# pla251715.net
KiCad netlist of a schematic drawn in EAGLE
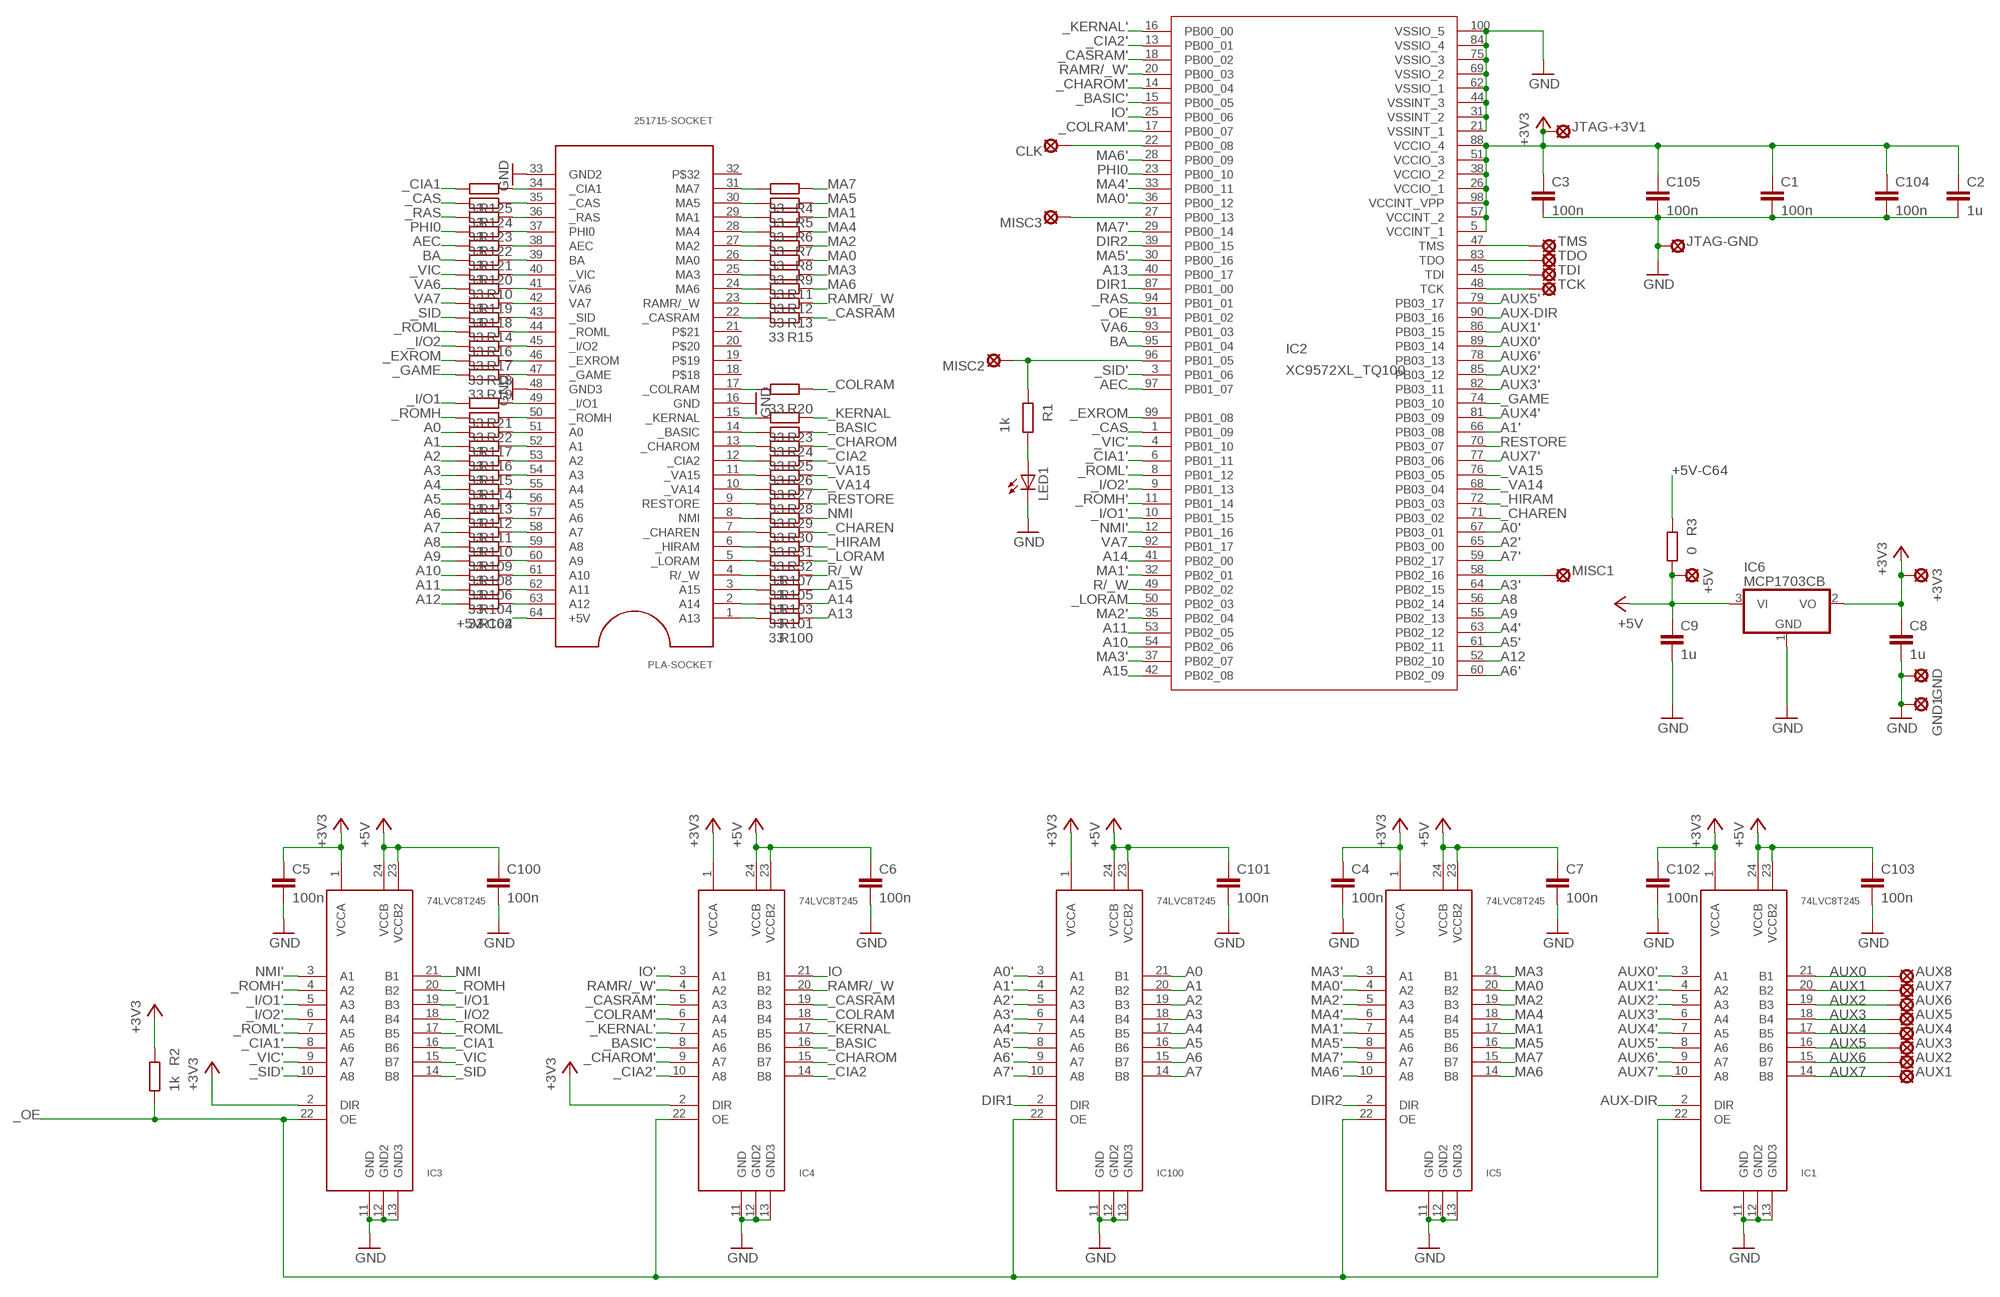
[diagram p0: schematic, sheet 1]

(export (version "E")
  (design (tool "Eeschema 10.0.6"))
  (components
    (comp (ref "+3V3")
      (value "LSP10")
      (footprint "eagle-import:LSP10")
      (libsource (lib "eagle-import") (part "LSP10"))
    )
    (comp (ref "+5V")
      (value "LSP10")
      (footprint "eagle-import:LSP10")
      (libsource (lib "eagle-import") (part "LSP10"))
    )
    (comp (ref "AUX1")
      (value "LSP10")
      (footprint "eagle-import:LSP10")
      (libsource (lib "eagle-import") (part "LSP10"))
    )
    (comp (ref "AUX2")
      (value "LSP10")
      (footprint "eagle-import:LSP10")
      (libsource (lib "eagle-import") (part "LSP10"))
    )
    (comp (ref "AUX3")
      (value "LSP10")
      (footprint "eagle-import:LSP10")
      (libsource (lib "eagle-import") (part "LSP10"))
    )
    (comp (ref "AUX4")
      (value "LSP10")
      (footprint "eagle-import:LSP10")
      (libsource (lib "eagle-import") (part "LSP10"))
    )
    (comp (ref "AUX5")
      (value "LSP10")
      (footprint "eagle-import:LSP10")
      (libsource (lib "eagle-import") (part "LSP10"))
    )
    (comp (ref "AUX6")
      (value "LSP10")
      (footprint "eagle-import:LSP10")
      (libsource (lib "eagle-import") (part "LSP10"))
    )
    (comp (ref "AUX7")
      (value "LSP10")
      (footprint "eagle-import:LSP10")
      (libsource (lib "eagle-import") (part "LSP10"))
    )
    (comp (ref "AUX8")
      (value "LSP10")
      (footprint "eagle-import:LSP10")
      (libsource (lib "eagle-import") (part "LSP10"))
    )
    (comp (ref "C1")
      (value "100n")
      (footprint "eagle-import:C0603")
      (libsource (lib "eagle-import") (part "C-EUC0603"))
    )
    (comp (ref "C2")
      (value "1u")
      (footprint "eagle-import:C1210")
      (libsource (lib "eagle-import") (part "C-EUC1210"))
    )
    (comp (ref "C3")
      (value "100n")
      (footprint "eagle-import:C0603")
      (libsource (lib "eagle-import") (part "C-EUC0603"))
    )
    (comp (ref "C4")
      (value "100n")
      (footprint "eagle-import:C0603")
      (libsource (lib "eagle-import") (part "C-EUC0603"))
    )
    (comp (ref "C5")
      (value "100n")
      (footprint "eagle-import:C0603")
      (libsource (lib "eagle-import") (part "C-EUC0603"))
    )
    (comp (ref "C6")
      (value "100n")
      (footprint "eagle-import:C0603")
      (libsource (lib "eagle-import") (part "C-EUC0603"))
    )
    (comp (ref "C7")
      (value "100n")
      (footprint "eagle-import:C0603")
      (libsource (lib "eagle-import") (part "C-EUC0603"))
    )
    (comp (ref "C8")
      (value "1u")
      (footprint "eagle-import:C1210")
      (libsource (lib "eagle-import") (part "C-EUC1210"))
    )
    (comp (ref "C9")
      (value "1u")
      (footprint "eagle-import:C1210")
      (libsource (lib "eagle-import") (part "C-EUC1210"))
    )
    (comp (ref "C100")
      (value "100n")
      (footprint "eagle-import:C0603")
      (libsource (lib "eagle-import") (part "C-EUC0603"))
    )
    (comp (ref "C101")
      (value "100n")
      (footprint "eagle-import:C0603")
      (libsource (lib "eagle-import") (part "C-EUC0603"))
    )
    (comp (ref "C102")
      (value "100n")
      (footprint "eagle-import:C0603")
      (libsource (lib "eagle-import") (part "C-EUC0603"))
    )
    (comp (ref "C103")
      (value "100n")
      (footprint "eagle-import:C0603")
      (libsource (lib "eagle-import") (part "C-EUC0603"))
    )
    (comp (ref "C104")
      (value "100n")
      (footprint "eagle-import:C0603")
      (libsource (lib "eagle-import") (part "C-EUC0603"))
    )
    (comp (ref "C105")
      (value "100n")
      (footprint "eagle-import:C0603")
      (libsource (lib "eagle-import") (part "C-EUC0603"))
    )
    (comp (ref "CLK")
      (value "LSP10")
      (footprint "eagle-import:LSP10")
      (libsource (lib "eagle-import") (part "LSP10"))
    )
    (comp (ref "GND")
      (value "LSP10")
      (footprint "eagle-import:LSP10")
      (libsource (lib "eagle-import") (part "LSP10"))
    )
    (comp (ref "GND1")
      (value "LSP10")
      (footprint "eagle-import:LSP10")
      (libsource (lib "eagle-import") (part "LSP10"))
    )
    (comp (ref "IC1")
      (value "74LVC8T245")
      (footprint "eagle-import:TSSOP24")
      (libsource (lib "eagle-import") (part "74LVC8T245"))
    )
    (comp (ref "IC2")
      (value "XC9572XL_TQ100")
      (footprint "eagle-import:TQ100")
      (libsource (lib "eagle-import") (part "XC9572XL_TQ100"))
    )
    (comp (ref "IC3")
      (value "74LVC8T245")
      (footprint "eagle-import:TSSOP24")
      (libsource (lib "eagle-import") (part "74LVC8T245"))
    )
    (comp (ref "IC4")
      (value "74LVC8T245")
      (footprint "eagle-import:TSSOP24")
      (libsource (lib "eagle-import") (part "74LVC8T245"))
    )
    (comp (ref "IC5")
      (value "74LVC8T245")
      (footprint "eagle-import:TSSOP24")
      (libsource (lib "eagle-import") (part "74LVC8T245"))
    )
    (comp (ref "IC6")
      (value "MCP1703CB")
      (footprint "eagle-import:SOT23")
      (libsource (lib "eagle-import") (part "MCP1703CB"))
    )
    (comp (ref "IC100")
      (value "74LVC8T245")
      (footprint "eagle-import:TSSOP24")
      (libsource (lib "eagle-import") (part "74LVC8T245"))
    )
    (comp (ref "JTAG-+3V1")
      (value "LSP10")
      (footprint "eagle-import:LSP10")
      (libsource (lib "eagle-import") (part "LSP10"))
    )
    (comp (ref "JTAG-GND")
      (value "LSP10")
      (footprint "eagle-import:LSP10")
      (libsource (lib "eagle-import") (part "LSP10"))
    )
    (comp (ref "LED1")
      (value "LED5MM")
      (footprint "eagle-import:LED5MM")
      (libsource (lib "eagle-import") (part "LED5MM"))
    )
    (comp (ref "MISC1")
      (value "LSP10")
      (footprint "eagle-import:LSP10")
      (libsource (lib "eagle-import") (part "LSP10"))
    )
    (comp (ref "MISC2")
      (value "LSP10")
      (footprint "eagle-import:LSP10")
      (libsource (lib "eagle-import") (part "LSP10"))
    )
    (comp (ref "MISC3")
      (value "LSP10")
      (footprint "eagle-import:LSP10")
      (libsource (lib "eagle-import") (part "LSP10"))
    )
    (comp (ref "PLA-SOCKET")
      (value "251715-SOCKET")
      (footprint "eagle-import:64-SPDIP")
      (libsource (lib "eagle-import") (part "251715-SOCKET"))
    )
    (comp (ref "R1")
      (value "1k")
      (footprint "eagle-import:R0805")
      (libsource (lib "eagle-import") (part "R-EU_R0805"))
    )
    (comp (ref "R2")
      (value "1k")
      (footprint "eagle-import:R0805")
      (libsource (lib "eagle-import") (part "R-EU_R0805"))
    )
    (comp (ref "R3")
      (value "0")
      (footprint "eagle-import:R0805")
      (libsource (lib "eagle-import") (part "R-EU_R0805"))
    )
    (comp (ref "R4")
      (value "33")
      (footprint "eagle-import:R0402")
      (libsource (lib "eagle-import") (part "R-EU_R0402"))
    )
    (comp (ref "R5")
      (value "33")
      (footprint "eagle-import:R0402")
      (libsource (lib "eagle-import") (part "R-EU_R0402"))
    )
    (comp (ref "R6")
      (value "33")
      (footprint "eagle-import:R0402")
      (libsource (lib "eagle-import") (part "R-EU_R0402"))
    )
    (comp (ref "R7")
      (value "33")
      (footprint "eagle-import:R0402")
      (libsource (lib "eagle-import") (part "R-EU_R0402"))
    )
    (comp (ref "R8")
      (value "33")
      (footprint "eagle-import:R0402")
      (libsource (lib "eagle-import") (part "R-EU_R0402"))
    )
    (comp (ref "R9")
      (value "33")
      (footprint "eagle-import:R0402")
      (libsource (lib "eagle-import") (part "R-EU_R0402"))
    )
    (comp (ref "R10")
      (value "33")
      (footprint "eagle-import:R0402")
      (libsource (lib "eagle-import") (part "R-EU_R0402"))
    )
    (comp (ref "R11")
      (value "33")
      (footprint "eagle-import:R0402")
      (libsource (lib "eagle-import") (part "R-EU_R0402"))
    )
    (comp (ref "R12")
      (value "33")
      (footprint "eagle-import:R0402")
      (libsource (lib "eagle-import") (part "R-EU_R0402"))
    )
    (comp (ref "R13")
      (value "33")
      (footprint "eagle-import:R0402")
      (libsource (lib "eagle-import") (part "R-EU_R0402"))
    )
    (comp (ref "R14")
      (value "33")
      (footprint "eagle-import:R0402")
      (libsource (lib "eagle-import") (part "R-EU_R0402"))
    )
    (comp (ref "R15")
      (value "33")
      (footprint "eagle-import:R0402")
      (libsource (lib "eagle-import") (part "R-EU_R0402"))
    )
    (comp (ref "R16")
      (value "33")
      (footprint "eagle-import:R0402")
      (libsource (lib "eagle-import") (part "R-EU_R0402"))
    )
    (comp (ref "R17")
      (value "33")
      (footprint "eagle-import:R0402")
      (libsource (lib "eagle-import") (part "R-EU_R0402"))
    )
    (comp (ref "R18")
      (value "33")
      (footprint "eagle-import:R0402")
      (libsource (lib "eagle-import") (part "R-EU_R0402"))
    )
    (comp (ref "R19")
      (value "33")
      (footprint "eagle-import:R0402")
      (libsource (lib "eagle-import") (part "R-EU_R0402"))
    )
    (comp (ref "R20")
      (value "33")
      (footprint "eagle-import:R0402")
      (libsource (lib "eagle-import") (part "R-EU_R0402"))
    )
    (comp (ref "R21")
      (value "33")
      (footprint "eagle-import:R0402")
      (libsource (lib "eagle-import") (part "R-EU_R0402"))
    )
    (comp (ref "R22")
      (value "33")
      (footprint "eagle-import:R0402")
      (libsource (lib "eagle-import") (part "R-EU_R0402"))
    )
    (comp (ref "R23")
      (value "33")
      (footprint "eagle-import:R0402")
      (libsource (lib "eagle-import") (part "R-EU_R0402"))
    )
    (comp (ref "R24")
      (value "33")
      (footprint "eagle-import:R0402")
      (libsource (lib "eagle-import") (part "R-EU_R0402"))
    )
    (comp (ref "R25")
      (value "33")
      (footprint "eagle-import:R0402")
      (libsource (lib "eagle-import") (part "R-EU_R0402"))
    )
    (comp (ref "R26")
      (value "33")
      (footprint "eagle-import:R0402")
      (libsource (lib "eagle-import") (part "R-EU_R0402"))
    )
    (comp (ref "R27")
      (value "33")
      (footprint "eagle-import:R0402")
      (libsource (lib "eagle-import") (part "R-EU_R0402"))
    )
    (comp (ref "R28")
      (value "33")
      (footprint "eagle-import:R0402")
      (libsource (lib "eagle-import") (part "R-EU_R0402"))
    )
    (comp (ref "R29")
      (value "33")
      (footprint "eagle-import:R0402")
      (libsource (lib "eagle-import") (part "R-EU_R0402"))
    )
    (comp (ref "R30")
      (value "33")
      (footprint "eagle-import:R0402")
      (libsource (lib "eagle-import") (part "R-EU_R0402"))
    )
    (comp (ref "R31")
      (value "33")
      (footprint "eagle-import:R0402")
      (libsource (lib "eagle-import") (part "R-EU_R0402"))
    )
    (comp (ref "R32")
      (value "33")
      (footprint "eagle-import:R0402")
      (libsource (lib "eagle-import") (part "R-EU_R0402"))
    )
    (comp (ref "R100")
      (value "33")
      (footprint "eagle-import:R0402")
      (libsource (lib "eagle-import") (part "R-EU_R0402"))
    )
    (comp (ref "R101")
      (value "33")
      (footprint "eagle-import:R0402")
      (libsource (lib "eagle-import") (part "R-EU_R0402"))
    )
    (comp (ref "R102")
      (value "33")
      (footprint "eagle-import:R0402")
      (libsource (lib "eagle-import") (part "R-EU_R0402"))
    )
    (comp (ref "R103")
      (value "33")
      (footprint "eagle-import:R0402")
      (libsource (lib "eagle-import") (part "R-EU_R0402"))
    )
    (comp (ref "R104")
      (value "33")
      (footprint "eagle-import:R0402")
      (libsource (lib "eagle-import") (part "R-EU_R0402"))
    )
    (comp (ref "R105")
      (value "33")
      (footprint "eagle-import:R0402")
      (libsource (lib "eagle-import") (part "R-EU_R0402"))
    )
    (comp (ref "R106")
      (value "33")
      (footprint "eagle-import:R0402")
      (libsource (lib "eagle-import") (part "R-EU_R0402"))
    )
    (comp (ref "R107")
      (value "33")
      (footprint "eagle-import:R0402")
      (libsource (lib "eagle-import") (part "R-EU_R0402"))
    )
    (comp (ref "R108")
      (value "33")
      (footprint "eagle-import:R0402")
      (libsource (lib "eagle-import") (part "R-EU_R0402"))
    )
    (comp (ref "R109")
      (value "33")
      (footprint "eagle-import:R0402")
      (libsource (lib "eagle-import") (part "R-EU_R0402"))
    )
    (comp (ref "R110")
      (value "33")
      (footprint "eagle-import:R0402")
      (libsource (lib "eagle-import") (part "R-EU_R0402"))
    )
    (comp (ref "R111")
      (value "33")
      (footprint "eagle-import:R0402")
      (libsource (lib "eagle-import") (part "R-EU_R0402"))
    )
    (comp (ref "R112")
      (value "33")
      (footprint "eagle-import:R0402")
      (libsource (lib "eagle-import") (part "R-EU_R0402"))
    )
    (comp (ref "R113")
      (value "33")
      (footprint "eagle-import:R0402")
      (libsource (lib "eagle-import") (part "R-EU_R0402"))
    )
    (comp (ref "R114")
      (value "33")
      (footprint "eagle-import:R0402")
      (libsource (lib "eagle-import") (part "R-EU_R0402"))
    )
    (comp (ref "R115")
      (value "33")
      (footprint "eagle-import:R0402")
      (libsource (lib "eagle-import") (part "R-EU_R0402"))
    )
    (comp (ref "R116")
      (value "33")
      (footprint "eagle-import:R0402")
      (libsource (lib "eagle-import") (part "R-EU_R0402"))
    )
    (comp (ref "R117")
      (value "33")
      (footprint "eagle-import:R0402")
      (libsource (lib "eagle-import") (part "R-EU_R0402"))
    )
    (comp (ref "R118")
      (value "33")
      (footprint "eagle-import:R0402")
      (libsource (lib "eagle-import") (part "R-EU_R0402"))
    )
    (comp (ref "R119")
      (value "33")
      (footprint "eagle-import:R0402")
      (libsource (lib "eagle-import") (part "R-EU_R0402"))
    )
    (comp (ref "R120")
      (value "33")
      (footprint "eagle-import:R0402")
      (libsource (lib "eagle-import") (part "R-EU_R0402"))
    )
    (comp (ref "R121")
      (value "33")
      (footprint "eagle-import:R0402")
      (libsource (lib "eagle-import") (part "R-EU_R0402"))
    )
    (comp (ref "R122")
      (value "33")
      (footprint "eagle-import:R0402")
      (libsource (lib "eagle-import") (part "R-EU_R0402"))
    )
    (comp (ref "R123")
      (value "33")
      (footprint "eagle-import:R0402")
      (libsource (lib "eagle-import") (part "R-EU_R0402"))
    )
    (comp (ref "R124")
      (value "33")
      (footprint "eagle-import:R0402")
      (libsource (lib "eagle-import") (part "R-EU_R0402"))
    )
    (comp (ref "R125")
      (value "33")
      (footprint "eagle-import:R0402")
      (libsource (lib "eagle-import") (part "R-EU_R0402"))
    )
    (comp (ref "TCK")
      (value "LSP10")
      (footprint "eagle-import:LSP10")
      (libsource (lib "eagle-import") (part "LSP10"))
    )
    (comp (ref "TDI")
      (value "LSP10")
      (footprint "eagle-import:LSP10")
      (libsource (lib "eagle-import") (part "LSP10"))
    )
    (comp (ref "TDO")
      (value "LSP10")
      (footprint "eagle-import:LSP10")
      (libsource (lib "eagle-import") (part "LSP10"))
    )
    (comp (ref "TMS")
      (value "LSP10")
      (footprint "eagle-import:LSP10")
      (libsource (lib "eagle-import") (part "LSP10"))
    )
  )
  (nets
    (net (code "1") (name "+3V3") (class "Default")
      (node (ref "+3V3") (pin "MP") (pinfunction "MP_MP") (pintype "passive"))
      (node (ref "C1") (pin "1") (pinfunction "1_1") (pintype "passive"))
      (node (ref "C102") (pin "1") (pinfunction "1_1") (pintype "passive"))
      (node (ref "C104") (pin "1") (pinfunction "1_1") (pintype "passive"))
      (node (ref "C105") (pin "1") (pinfunction "1_1") (pintype "passive"))
      (node (ref "C2") (pin "1") (pinfunction "1_1") (pintype "passive"))
      (node (ref "C3") (pin "1") (pinfunction "1_1") (pintype "passive"))
      (node (ref "C4") (pin "1") (pinfunction "1_1") (pintype "passive"))
      (node (ref "C5") (pin "1") (pinfunction "1_1") (pintype "passive"))
      (node (ref "C8") (pin "1") (pinfunction "1_1") (pintype "passive"))
      (node (ref "IC1") (pin "1") (pinfunction "VCCA_1") (pintype "bidirectional"))
      (node (ref "IC100") (pin "1") (pinfunction "VCCA_1") (pintype "bidirectional"))
      (node (ref "IC2") (pin "26") (pinfunction "VCCIO_1_26") (pintype "passive"))
      (node (ref "IC2") (pin "38") (pinfunction "VCCIO_2_38") (pintype "passive"))
      (node (ref "IC2") (pin "5") (pinfunction "VCCINT_1_5") (pintype "passive"))
      (node (ref "IC2") (pin "51") (pinfunction "VCCIO_3_51") (pintype "passive"))
      (node (ref "IC2") (pin "57") (pinfunction "VCCINT_2_57") (pintype "passive"))
      (node (ref "IC2") (pin "88") (pinfunction "VCCIO_4_88") (pintype "passive"))
      (node (ref "IC2") (pin "98") (pinfunction "VCCINT_VPP_98") (pintype "passive"))
      (node (ref "IC3") (pin "1") (pinfunction "VCCA_1") (pintype "bidirectional"))
      (node (ref "IC3") (pin "2") (pinfunction "DIR_2") (pintype "bidirectional"))
      (node (ref "IC4") (pin "1") (pinfunction "VCCA_1") (pintype "bidirectional"))
      (node (ref "IC4") (pin "2") (pinfunction "DIR_2") (pintype "bidirectional"))
      (node (ref "IC5") (pin "1") (pinfunction "VCCA_1") (pintype "bidirectional"))
      (node (ref "IC6") (pin "2") (pinfunction "VO_2") (pintype "passive"))
      (node (ref "JTAG-+3V1") (pin "MP") (pinfunction "MP_MP") (pintype "passive"))
      (node (ref "R2") (pin "1") (pinfunction "1_1") (pintype "passive"))
    )
    (net (code "2") (name "+5V") (class "Default")
      (node (ref "+5V") (pin "MP") (pinfunction "MP_MP") (pintype "passive"))
      (node (ref "C100") (pin "1") (pinfunction "1_1") (pintype "passive"))
      (node (ref "C101") (pin "1") (pinfunction "1_1") (pintype "passive"))
      (node (ref "C103") (pin "1") (pinfunction "1_1") (pintype "passive"))
      (node (ref "C6") (pin "1") (pinfunction "1_1") (pintype "passive"))
      (node (ref "C7") (pin "1") (pinfunction "1_1") (pintype "passive"))
      (node (ref "C9") (pin "1") (pinfunction "1_1") (pintype "passive"))
      (node (ref "IC1") (pin "23") (pinfunction "VCCB2_23") (pintype "bidirectional"))
      (node (ref "IC1") (pin "24") (pinfunction "VCCB_24") (pintype "bidirectional"))
      (node (ref "IC100") (pin "23") (pinfunction "VCCB2_23") (pintype "bidirectional"))
      (node (ref "IC100") (pin "24") (pinfunction "VCCB_24") (pintype "bidirectional"))
      (node (ref "IC3") (pin "23") (pinfunction "VCCB2_23") (pintype "bidirectional"))
      (node (ref "IC3") (pin "24") (pinfunction "VCCB_24") (pintype "bidirectional"))
      (node (ref "IC4") (pin "23") (pinfunction "VCCB2_23") (pintype "bidirectional"))
      (node (ref "IC4") (pin "24") (pinfunction "VCCB_24") (pintype "bidirectional"))
      (node (ref "IC5") (pin "23") (pinfunction "VCCB2_23") (pintype "bidirectional"))
      (node (ref "IC5") (pin "24") (pinfunction "VCCB_24") (pintype "bidirectional"))
      (node (ref "IC6") (pin "3") (pinfunction "VI_3") (pintype "input"))
      (node (ref "R3") (pin "2") (pinfunction "2_2") (pintype "passive"))
    )
    (net (code "3") (name "/+5V-C64") (class "Default")
      (node (ref "PLA-SOCKET") (pin "64") (pinfunction "+5V_64") (pintype "bidirectional"))
      (node (ref "R3") (pin "1") (pinfunction "1_1") (pintype "passive"))
    )
    (net (code "4") (name "/A0") (class "Default")
      (node (ref "IC100") (pin "21") (pinfunction "B1_21") (pintype "bidirectional"))
      (node (ref "R117") (pin "2") (pinfunction "2_2") (pintype "passive"))
    )
    (net (code "5") (name "/A0'") (class "Default")
      (node (ref "IC100") (pin "3") (pinfunction "A1_3") (pintype "bidirectional"))
      (node (ref "IC2") (pin "67") (pinfunction "PB03_01_67") (pintype "bidirectional"))
    )
    (net (code "6") (name "/A1") (class "Default")
      (node (ref "IC100") (pin "20") (pinfunction "B2_20") (pintype "bidirectional"))
      (node (ref "R116") (pin "2") (pinfunction "2_2") (pintype "passive"))
    )
    (net (code "7") (name "/A1'") (class "Default")
      (node (ref "IC100") (pin "4") (pinfunction "A2_4") (pintype "bidirectional"))
      (node (ref "IC2") (pin "66") (pinfunction "PB03_08_66") (pintype "bidirectional"))
    )
    (net (code "8") (name "/A2") (class "Default")
      (node (ref "IC100") (pin "19") (pinfunction "B3_19") (pintype "bidirectional"))
      (node (ref "R115") (pin "2") (pinfunction "2_2") (pintype "passive"))
    )
    (net (code "9") (name "/A2'") (class "Default")
      (node (ref "IC100") (pin "5") (pinfunction "A3_5") (pintype "bidirectional"))
      (node (ref "IC2") (pin "65") (pinfunction "PB03_00_65") (pintype "bidirectional"))
    )
    (net (code "10") (name "/A3") (class "Default")
      (node (ref "IC100") (pin "18") (pinfunction "B4_18") (pintype "bidirectional"))
      (node (ref "R114") (pin "2") (pinfunction "2_2") (pintype "passive"))
    )
    (net (code "11") (name "/A3'") (class "Default")
      (node (ref "IC100") (pin "6") (pinfunction "A4_6") (pintype "bidirectional"))
      (node (ref "IC2") (pin "64") (pinfunction "PB02_15_64") (pintype "bidirectional"))
    )
    (net (code "12") (name "/A4") (class "Default")
      (node (ref "IC100") (pin "17") (pinfunction "B5_17") (pintype "bidirectional"))
      (node (ref "R113") (pin "2") (pinfunction "2_2") (pintype "passive"))
    )
    (net (code "13") (name "/A4'") (class "Default")
      (node (ref "IC100") (pin "7") (pinfunction "A5_7") (pintype "bidirectional"))
      (node (ref "IC2") (pin "63") (pinfunction "PB02_12_63") (pintype "bidirectional"))
    )
    (net (code "14") (name "/A5") (class "Default")
      (node (ref "IC100") (pin "16") (pinfunction "B6_16") (pintype "bidirectional"))
      (node (ref "R112") (pin "2") (pinfunction "2_2") (pintype "passive"))
    )
    (net (code "15") (name "/A5'") (class "Default")
      (node (ref "IC100") (pin "8") (pinfunction "A6_8") (pintype "bidirectional"))
      (node (ref "IC2") (pin "61") (pinfunction "PB02_11_61") (pintype "bidirectional"))
    )
    (net (code "16") (name "/A6") (class "Default")
      (node (ref "IC100") (pin "15") (pinfunction "B7_15") (pintype "bidirectional"))
      (node (ref "R111") (pin "2") (pinfunction "2_2") (pintype "passive"))
    )
    (net (code "17") (name "/A6'") (class "Default")
      (node (ref "IC100") (pin "9") (pinfunction "A7_9") (pintype "bidirectional"))
      (node (ref "IC2") (pin "60") (pinfunction "PB02_09_60") (pintype "bidirectional"))
    )
    (net (code "18") (name "/A7") (class "Default")
      (node (ref "IC100") (pin "14") (pinfunction "B8_14") (pintype "bidirectional"))
      (node (ref "R110") (pin "2") (pinfunction "2_2") (pintype "passive"))
    )
    (net (code "19") (name "/A7'") (class "Default")
      (node (ref "IC100") (pin "10") (pinfunction "A8_10") (pintype "bidirectional"))
      (node (ref "IC2") (pin "59") (pinfunction "PB02_17_59") (pintype "bidirectional"))
    )
    (net (code "20") (name "/A8") (class "Default")
      (node (ref "IC2") (pin "56") (pinfunction "PB02_14_56") (pintype "bidirectional"))
      (node (ref "R109") (pin "2") (pinfunction "2_2") (pintype "passive"))
    )
    (net (code "21") (name "/A9") (class "Default")
      (node (ref "IC2") (pin "55") (pinfunction "PB02_13_55") (pintype "bidirectional"))
      (node (ref "R108") (pin "2") (pinfunction "2_2") (pintype "passive"))
    )
    (net (code "22") (name "/A10") (class "Default")
      (node (ref "IC2") (pin "54") (pinfunction "PB02_06_54") (pintype "bidirectional"))
      (node (ref "R106") (pin "2") (pinfunction "2_2") (pintype "passive"))
    )
    (net (code "23") (name "/A11") (class "Default")
      (node (ref "IC2") (pin "53") (pinfunction "PB02_05_53") (pintype "bidirectional"))
      (node (ref "R104") (pin "2") (pinfunction "2_2") (pintype "passive"))
    )
    (net (code "24") (name "/A12") (class "Default")
      (node (ref "IC2") (pin "52") (pinfunction "PB02_10_52") (pintype "bidirectional"))
      (node (ref "R102") (pin "2") (pinfunction "2_2") (pintype "passive"))
    )
    (net (code "25") (name "/A13") (class "Default")
      (node (ref "IC2") (pin "40") (pinfunction "PB00_17_40") (pintype "bidirectional"))
      (node (ref "R100") (pin "1") (pinfunction "1_1") (pintype "passive"))
    )
    (net (code "26") (name "/A14") (class "Default")
      (node (ref "IC2") (pin "41") (pinfunction "PB02_00_41") (pintype "bidirectional"))
      (node (ref "R101") (pin "1") (pinfunction "1_1") (pintype "passive"))
    )
    (net (code "27") (name "/A15") (class "Default")
      (node (ref "IC2") (pin "42") (pinfunction "PB02_08_42") (pintype "bidirectional"))
      (node (ref "R103") (pin "1") (pinfunction "1_1") (pintype "passive"))
    )
    (net (code "28") (name "/AEC") (class "Default")
      (node (ref "IC2") (pin "97") (pinfunction "PB01_07_97") (pintype "bidirectional"))
      (node (ref "R121") (pin "2") (pinfunction "2_2") (pintype "passive"))
    )
    (net (code "29") (name "/AUX-DIR") (class "Default")
      (node (ref "IC1") (pin "2") (pinfunction "DIR_2") (pintype "bidirectional"))
      (node (ref "IC2") (pin "90") (pinfunction "PB03_16_90") (pintype "bidirectional"))
    )
    (net (code "30") (name "/AUX0") (class "Default")
      (node (ref "AUX8") (pin "MP") (pinfunction "MP_MP") (pintype "passive"))
      (node (ref "IC1") (pin "21") (pinfunction "B1_21") (pintype "bidirectional"))
    )
    (net (code "31") (name "/AUX0'") (class "Default")
      (node (ref "IC1") (pin "3") (pinfunction "A1_3") (pintype "bidirectional"))
      (node (ref "IC2") (pin "89") (pinfunction "PB03_14_89") (pintype "bidirectional"))
    )
    (net (code "32") (name "/AUX1") (class "Default")
      (node (ref "AUX7") (pin "MP") (pinfunction "MP_MP") (pintype "passive"))
      (node (ref "IC1") (pin "20") (pinfunction "B2_20") (pintype "bidirectional"))
    )
    (net (code "33") (name "/AUX1'") (class "Default")
      (node (ref "IC1") (pin "4") (pinfunction "A2_4") (pintype "bidirectional"))
      (node (ref "IC2") (pin "86") (pinfunction "PB03_15_86") (pintype "bidirectional"))
    )
    (net (code "34") (name "/AUX2") (class "Default")
      (node (ref "AUX6") (pin "MP") (pinfunction "MP_MP") (pintype "passive"))
      (node (ref "IC1") (pin "19") (pinfunction "B3_19") (pintype "bidirectional"))
    )
    (net (code "35") (name "/AUX2'") (class "Default")
      (node (ref "IC1") (pin "5") (pinfunction "A3_5") (pintype "bidirectional"))
      (node (ref "IC2") (pin "85") (pinfunction "PB03_12_85") (pintype "bidirectional"))
    )
    (net (code "36") (name "/AUX3") (class "Default")
      (node (ref "AUX5") (pin "MP") (pinfunction "MP_MP") (pintype "passive"))
      (node (ref "IC1") (pin "18") (pinfunction "B4_18") (pintype "bidirectional"))
    )
    (net (code "37") (name "/AUX3'") (class "Default")
      (node (ref "IC1") (pin "6") (pinfunction "A4_6") (pintype "bidirectional"))
      (node (ref "IC2") (pin "82") (pinfunction "PB03_11_82") (pintype "bidirectional"))
    )
    (net (code "38") (name "/AUX4") (class "Default")
      (node (ref "AUX4") (pin "MP") (pinfunction "MP_MP") (pintype "passive"))
      (node (ref "IC1") (pin "17") (pinfunction "B5_17") (pintype "bidirectional"))
    )
    (net (code "39") (name "/AUX4'") (class "Default")
      (node (ref "IC1") (pin "7") (pinfunction "A5_7") (pintype "bidirectional"))
      (node (ref "IC2") (pin "81") (pinfunction "PB03_09_81") (pintype "bidirectional"))
    )
    (net (code "40") (name "/AUX5") (class "Default")
      (node (ref "AUX3") (pin "MP") (pinfunction "MP_MP") (pintype "passive"))
      (node (ref "IC1") (pin "16") (pinfunction "B6_16") (pintype "bidirectional"))
    )
    (net (code "41") (name "/AUX5'") (class "Default")
      (node (ref "IC1") (pin "8") (pinfunction "A6_8") (pintype "bidirectional"))
      (node (ref "IC2") (pin "79") (pinfunction "PB03_17_79") (pintype "bidirectional"))
    )
    (net (code "42") (name "/AUX6") (class "Default")
      (node (ref "AUX2") (pin "MP") (pinfunction "MP_MP") (pintype "passive"))
      (node (ref "IC1") (pin "15") (pinfunction "B7_15") (pintype "bidirectional"))
    )
    (net (code "43") (name "/AUX6'") (class "Default")
      (node (ref "IC1") (pin "9") (pinfunction "A7_9") (pintype "bidirectional"))
      (node (ref "IC2") (pin "78") (pinfunction "PB03_13_78") (pintype "bidirectional"))
    )
    (net (code "44") (name "/AUX7") (class "Default")
      (node (ref "AUX1") (pin "MP") (pinfunction "MP_MP") (pintype "passive"))
      (node (ref "IC1") (pin "14") (pinfunction "B8_14") (pintype "bidirectional"))
    )
    (net (code "45") (name "/AUX7'") (class "Default")
      (node (ref "IC1") (pin "10") (pinfunction "A8_10") (pintype "bidirectional"))
      (node (ref "IC2") (pin "77") (pinfunction "PB03_06_77") (pintype "bidirectional"))
    )
    (net (code "46") (name "/BA") (class "Default")
      (node (ref "IC2") (pin "95") (pinfunction "PB01_04_95") (pintype "bidirectional"))
      (node (ref "R120") (pin "2") (pinfunction "2_2") (pintype "passive"))
    )
    (net (code "47") (name "/DIR1") (class "Default")
      (node (ref "IC100") (pin "2") (pinfunction "DIR_2") (pintype "bidirectional"))
      (node (ref "IC2") (pin "87") (pinfunction "PB01_00_87") (pintype "bidirectional"))
    )
    (net (code "48") (name "/DIR2") (class "Default")
      (node (ref "IC2") (pin "39") (pinfunction "PB00_15_39") (pintype "bidirectional"))
      (node (ref "IC5") (pin "2") (pinfunction "DIR_2") (pintype "bidirectional"))
    )
    (net (code "49") (name "/IO") (class "Default")
      (node (ref "IC4") (pin "21") (pinfunction "B1_21") (pintype "bidirectional"))
    )
    (net (code "50") (name "/IO'") (class "Default")
      (node (ref "IC2") (pin "25") (pinfunction "PB00_06_25") (pintype "bidirectional"))
      (node (ref "IC4") (pin "3") (pinfunction "A1_3") (pintype "bidirectional"))
    )
    (net (code "51") (name "/MA0") (class "Default")
      (node (ref "IC5") (pin "20") (pinfunction "B2_20") (pintype "bidirectional"))
      (node (ref "R9") (pin "1") (pinfunction "1_1") (pintype "passive"))
    )
    (net (code "52") (name "/MA0'") (class "Default")
      (node (ref "IC2") (pin "36") (pinfunction "PB00_12_36") (pintype "bidirectional"))
      (node (ref "IC5") (pin "4") (pinfunction "A2_4") (pintype "bidirectional"))
    )
    (net (code "53") (name "/MA1") (class "Default")
      (node (ref "IC5") (pin "17") (pinfunction "B5_17") (pintype "bidirectional"))
      (node (ref "R6") (pin "1") (pinfunction "1_1") (pintype "passive"))
    )
    (net (code "54") (name "/MA1'") (class "Default")
      (node (ref "IC2") (pin "32") (pinfunction "PB02_01_32") (pintype "bidirectional"))
      (node (ref "IC5") (pin "7") (pinfunction "A5_7") (pintype "bidirectional"))
    )
    (net (code "55") (name "/MA2") (class "Default")
      (node (ref "IC5") (pin "19") (pinfunction "B3_19") (pintype "bidirectional"))
      (node (ref "R8") (pin "1") (pinfunction "1_1") (pintype "passive"))
    )
    (net (code "56") (name "/MA2'") (class "Default")
      (node (ref "IC2") (pin "35") (pinfunction "PB02_04_35") (pintype "bidirectional"))
      (node (ref "IC5") (pin "5") (pinfunction "A3_5") (pintype "bidirectional"))
    )
    (net (code "57") (name "/MA3") (class "Default")
      (node (ref "IC5") (pin "21") (pinfunction "B1_21") (pintype "bidirectional"))
      (node (ref "R11") (pin "1") (pinfunction "1_1") (pintype "passive"))
    )
    (net (code "58") (name "/MA3'") (class "Default")
      (node (ref "IC2") (pin "37") (pinfunction "PB02_07_37") (pintype "bidirectional"))
      (node (ref "IC5") (pin "3") (pinfunction "A1_3") (pintype "bidirectional"))
    )
    (net (code "59") (name "/MA4") (class "Default")
      (node (ref "IC5") (pin "18") (pinfunction "B4_18") (pintype "bidirectional"))
      (node (ref "R7") (pin "1") (pinfunction "1_1") (pintype "passive"))
    )
    (net (code "60") (name "/MA4'") (class "Default")
      (node (ref "IC2") (pin "33") (pinfunction "PB00_11_33") (pintype "bidirectional"))
      (node (ref "IC5") (pin "6") (pinfunction "A4_6") (pintype "bidirectional"))
    )
    (net (code "61") (name "/MA5") (class "Default")
      (node (ref "IC5") (pin "16") (pinfunction "B6_16") (pintype "bidirectional"))
      (node (ref "R5") (pin "1") (pinfunction "1_1") (pintype "passive"))
    )
    (net (code "62") (name "/MA5'") (class "Default")
      (node (ref "IC2") (pin "30") (pinfunction "PB00_16_30") (pintype "bidirectional"))
      (node (ref "IC5") (pin "8") (pinfunction "A6_8") (pintype "bidirectional"))
    )
    (net (code "63") (name "/MA6") (class "Default")
      (node (ref "IC5") (pin "14") (pinfunction "B8_14") (pintype "bidirectional"))
      (node (ref "R12") (pin "1") (pinfunction "1_1") (pintype "passive"))
    )
    (net (code "64") (name "/MA6'") (class "Default")
      (node (ref "IC2") (pin "28") (pinfunction "PB00_09_28") (pintype "bidirectional"))
      (node (ref "IC5") (pin "10") (pinfunction "A8_10") (pintype "bidirectional"))
    )
    (net (code "65") (name "/MA7") (class "Default")
      (node (ref "IC5") (pin "15") (pinfunction "B7_15") (pintype "bidirectional"))
      (node (ref "R4") (pin "1") (pinfunction "1_1") (pintype "passive"))
    )
    (net (code "66") (name "/MA7'") (class "Default")
      (node (ref "IC2") (pin "29") (pinfunction "PB00_14_29") (pintype "bidirectional"))
      (node (ref "IC5") (pin "9") (pinfunction "A7_9") (pintype "bidirectional"))
    )
    (net (code "67") (name "/NMI") (class "Default")
      (node (ref "IC3") (pin "21") (pinfunction "B1_21") (pintype "bidirectional"))
      (node (ref "R30") (pin "1") (pinfunction "1_1") (pintype "passive"))
    )
    (net (code "68") (name "/NMI'") (class "Default")
      (node (ref "IC2") (pin "12") (pinfunction "PB01_16_12") (pintype "bidirectional"))
      (node (ref "IC3") (pin "3") (pinfunction "A1_3") (pintype "bidirectional"))
    )
    (net (code "69") (name "/PHI0") (class "Default")
      (node (ref "IC2") (pin "23") (pinfunction "PB00_10_23") (pintype "bidirectional"))
      (node (ref "R122") (pin "2") (pinfunction "2_2") (pintype "passive"))
    )
    (net (code "70") (name "/RAMR{slash}_W") (class "Default")
      (node (ref "IC4") (pin "20") (pinfunction "B2_20") (pintype "bidirectional"))
      (node (ref "R13") (pin "1") (pinfunction "1_1") (pintype "passive"))
    )
    (net (code "71") (name "/RAMR{slash}_W'") (class "Default")
      (node (ref "IC2") (pin "20") (pinfunction "PB00_03_20") (pintype "bidirectional"))
      (node (ref "IC4") (pin "4") (pinfunction "A2_4") (pintype "bidirectional"))
    )
    (net (code "72") (name "/RESTORE") (class "Default")
      (node (ref "IC2") (pin "70") (pinfunction "PB03_07_70") (pintype "bidirectional"))
      (node (ref "R29") (pin "1") (pinfunction "1_1") (pintype "passive"))
    )
    (net (code "73") (name "/R{slash}_W") (class "Default")
      (node (ref "IC2") (pin "49") (pinfunction "PB02_02_49") (pintype "bidirectional"))
      (node (ref "R105") (pin "1") (pinfunction "1_1") (pintype "passive"))
    )
    (net (code "74") (name "/VA6") (class "Default")
      (node (ref "IC2") (pin "93") (pinfunction "PB01_03_93") (pintype "bidirectional"))
      (node (ref "R119") (pin "2") (pinfunction "2_2") (pintype "passive"))
    )
    (net (code "75") (name "/VA7") (class "Default")
      (node (ref "IC2") (pin "92") (pinfunction "PB01_17_92") (pintype "bidirectional"))
      (node (ref "R118") (pin "2") (pinfunction "2_2") (pintype "passive"))
    )
    (net (code "76") (name "/_BASIC") (class "Default")
      (node (ref "IC4") (pin "16") (pinfunction "B6_16") (pintype "bidirectional"))
      (node (ref "R24") (pin "1") (pinfunction "1_1") (pintype "passive"))
    )
    (net (code "77") (name "/_BASIC'") (class "Default")
      (node (ref "IC2") (pin "15") (pinfunction "PB00_05_15") (pintype "bidirectional"))
      (node (ref "IC4") (pin "8") (pinfunction "A6_8") (pintype "bidirectional"))
    )
    (net (code "78") (name "/_CAS") (class "Default")
      (node (ref "IC2") (pin "1") (pinfunction "PB01_09_1") (pintype "bidirectional"))
      (node (ref "R124") (pin "2") (pinfunction "2_2") (pintype "passive"))
    )
    (net (code "79") (name "/_CASRAM") (class "Default")
      (node (ref "IC4") (pin "19") (pinfunction "B3_19") (pintype "bidirectional"))
      (node (ref "R15") (pin "1") (pinfunction "1_1") (pintype "passive"))
    )
    (net (code "80") (name "/_CASRAM'") (class "Default")
      (node (ref "IC2") (pin "18") (pinfunction "PB00_02_18") (pintype "bidirectional"))
      (node (ref "IC4") (pin "5") (pinfunction "A3_5") (pintype "bidirectional"))
    )
    (net (code "81") (name "/_CHAREN") (class "Default")
      (node (ref "IC2") (pin "71") (pinfunction "PB03_02_71") (pintype "bidirectional"))
      (node (ref "R31") (pin "1") (pinfunction "1_1") (pintype "passive"))
    )
    (net (code "82") (name "/_CHAROM") (class "Default")
      (node (ref "IC4") (pin "15") (pinfunction "B7_15") (pintype "bidirectional"))
      (node (ref "R25") (pin "1") (pinfunction "1_1") (pintype "passive"))
    )
    (net (code "83") (name "/_CHAROM'") (class "Default")
      (node (ref "IC2") (pin "14") (pinfunction "PB00_04_14") (pintype "bidirectional"))
      (node (ref "IC4") (pin "9") (pinfunction "A7_9") (pintype "bidirectional"))
    )
    (net (code "84") (name "/_CIA1") (class "Default")
      (node (ref "IC3") (pin "16") (pinfunction "B6_16") (pintype "bidirectional"))
      (node (ref "R125") (pin "2") (pinfunction "2_2") (pintype "passive"))
    )
    (net (code "85") (name "/_CIA1'") (class "Default")
      (node (ref "IC2") (pin "6") (pinfunction "PB01_11_6") (pintype "bidirectional"))
      (node (ref "IC3") (pin "8") (pinfunction "A6_8") (pintype "bidirectional"))
    )
    (net (code "86") (name "/_CIA2") (class "Default")
      (node (ref "IC4") (pin "14") (pinfunction "B8_14") (pintype "bidirectional"))
      (node (ref "R26") (pin "1") (pinfunction "1_1") (pintype "passive"))
    )
    (net (code "87") (name "/_CIA2'") (class "Default")
      (node (ref "IC2") (pin "13") (pinfunction "PB00_01_13") (pintype "bidirectional"))
      (node (ref "IC4") (pin "10") (pinfunction "A8_10") (pintype "bidirectional"))
    )
    (net (code "88") (name "/_COLRAM") (class "Default")
      (node (ref "IC4") (pin "18") (pinfunction "B4_18") (pintype "bidirectional"))
      (node (ref "R20") (pin "1") (pinfunction "1_1") (pintype "passive"))
    )
    (net (code "89") (name "/_COLRAM'") (class "Default")
      (node (ref "IC2") (pin "17") (pinfunction "PB00_07_17") (pintype "bidirectional"))
      (node (ref "IC4") (pin "6") (pinfunction "A4_6") (pintype "bidirectional"))
    )
    (net (code "90") (name "/_EXROM") (class "Default")
      (node (ref "IC2") (pin "99") (pinfunction "PB01_08_99") (pintype "bidirectional"))
      (node (ref "R18") (pin "2") (pinfunction "2_2") (pintype "passive"))
    )
    (net (code "91") (name "/_GAME") (class "Default")
      (node (ref "IC2") (pin "74") (pinfunction "PB03_10_74") (pintype "bidirectional"))
      (node (ref "R19") (pin "2") (pinfunction "2_2") (pintype "passive"))
    )
    (net (code "92") (name "/_HIRAM") (class "Default")
      (node (ref "IC2") (pin "72") (pinfunction "PB03_03_72") (pintype "bidirectional"))
      (node (ref "R32") (pin "1") (pinfunction "1_1") (pintype "passive"))
    )
    (net (code "93") (name "/_I{slash}O1") (class "Default")
      (node (ref "IC3") (pin "19") (pinfunction "B3_19") (pintype "bidirectional"))
      (node (ref "R21") (pin "2") (pinfunction "2_2") (pintype "passive"))
    )
    (net (code "94") (name "/_I{slash}O1'") (class "Default")
      (node (ref "IC2") (pin "10") (pinfunction "PB01_15_10") (pintype "bidirectional"))
      (node (ref "IC3") (pin "5") (pinfunction "A3_5") (pintype "bidirectional"))
    )
    (net (code "95") (name "/_I{slash}O2") (class "Default")
      (node (ref "IC3") (pin "18") (pinfunction "B4_18") (pintype "bidirectional"))
      (node (ref "R17") (pin "2") (pinfunction "2_2") (pintype "passive"))
    )
    (net (code "96") (name "/_I{slash}O2'") (class "Default")
      (node (ref "IC2") (pin "9") (pinfunction "PB01_13_9") (pintype "bidirectional"))
      (node (ref "IC3") (pin "6") (pinfunction "A4_6") (pintype "bidirectional"))
    )
    (net (code "97") (name "/_KERNAL") (class "Default")
      (node (ref "IC4") (pin "17") (pinfunction "B5_17") (pintype "bidirectional"))
      (node (ref "R23") (pin "1") (pinfunction "1_1") (pintype "passive"))
    )
    (net (code "98") (name "/_KERNAL'") (class "Default")
      (node (ref "IC2") (pin "16") (pinfunction "PB00_00_16") (pintype "bidirectional"))
      (node (ref "IC4") (pin "7") (pinfunction "A5_7") (pintype "bidirectional"))
    )
    (net (code "99") (name "/_LORAM") (class "Default")
      (node (ref "IC2") (pin "50") (pinfunction "PB02_03_50") (pintype "bidirectional"))
      (node (ref "R107") (pin "1") (pinfunction "1_1") (pintype "passive"))
    )
    (net (code "100") (name "/_OE") (class "Default")
      (node (ref "IC1") (pin "22") (pinfunction "OE_22") (pintype "bidirectional"))
      (node (ref "IC100") (pin "22") (pinfunction "OE_22") (pintype "bidirectional"))
      (node (ref "IC2") (pin "91") (pinfunction "PB01_02_91") (pintype "bidirectional"))
      (node (ref "IC3") (pin "22") (pinfunction "OE_22") (pintype "bidirectional"))
      (node (ref "IC4") (pin "22") (pinfunction "OE_22") (pintype "bidirectional"))
      (node (ref "IC5") (pin "22") (pinfunction "OE_22") (pintype "bidirectional"))
      (node (ref "R2") (pin "2") (pinfunction "2_2") (pintype "passive"))
    )
    (net (code "101") (name "/_RAS") (class "Default")
      (node (ref "IC2") (pin "94") (pinfunction "PB01_01_94") (pintype "bidirectional"))
      (node (ref "R123") (pin "2") (pinfunction "2_2") (pintype "passive"))
    )
    (net (code "102") (name "/_ROMH") (class "Default")
      (node (ref "IC3") (pin "20") (pinfunction "B2_20") (pintype "bidirectional"))
      (node (ref "R22") (pin "2") (pinfunction "2_2") (pintype "passive"))
    )
    (net (code "103") (name "/_ROMH'") (class "Default")
      (node (ref "IC2") (pin "11") (pinfunction "PB01_14_11") (pintype "bidirectional"))
      (node (ref "IC3") (pin "4") (pinfunction "A2_4") (pintype "bidirectional"))
    )
    (net (code "104") (name "/_ROML") (class "Default")
      (node (ref "IC3") (pin "17") (pinfunction "B5_17") (pintype "bidirectional"))
      (node (ref "R16") (pin "2") (pinfunction "2_2") (pintype "passive"))
    )
    (net (code "105") (name "/_ROML'") (class "Default")
      (node (ref "IC2") (pin "8") (pinfunction "PB01_12_8") (pintype "bidirectional"))
      (node (ref "IC3") (pin "7") (pinfunction "A5_7") (pintype "bidirectional"))
    )
    (net (code "106") (name "/_SID") (class "Default")
      (node (ref "IC3") (pin "14") (pinfunction "B8_14") (pintype "bidirectional"))
      (node (ref "R14") (pin "2") (pinfunction "2_2") (pintype "passive"))
    )
    (net (code "107") (name "/_SID'") (class "Default")
      (node (ref "IC2") (pin "3") (pinfunction "PB01_06_3") (pintype "bidirectional"))
      (node (ref "IC3") (pin "10") (pinfunction "A8_10") (pintype "bidirectional"))
    )
    (net (code "108") (name "/_VA14") (class "Default")
      (node (ref "IC2") (pin "68") (pinfunction "PB03_04_68") (pintype "bidirectional"))
      (node (ref "R28") (pin "1") (pinfunction "1_1") (pintype "passive"))
    )
    (net (code "109") (name "/_VA15") (class "Default")
      (node (ref "IC2") (pin "76") (pinfunction "PB03_05_76") (pintype "bidirectional"))
      (node (ref "R27") (pin "1") (pinfunction "1_1") (pintype "passive"))
    )
    (net (code "110") (name "/_VIC") (class "Default")
      (node (ref "IC3") (pin "15") (pinfunction "B7_15") (pintype "bidirectional"))
      (node (ref "R10") (pin "2") (pinfunction "2_2") (pintype "passive"))
    )
    (net (code "111") (name "/_VIC'") (class "Default")
      (node (ref "IC2") (pin "4") (pinfunction "PB01_10_4") (pintype "bidirectional"))
      (node (ref "IC3") (pin "9") (pinfunction "A7_9") (pintype "bidirectional"))
    )
    (net (code "112") (name "GND") (class "Default")
      (node (ref "C1") (pin "2") (pinfunction "2_2") (pintype "passive"))
      (node (ref "C100") (pin "2") (pinfunction "2_2") (pintype "passive"))
      (node (ref "C101") (pin "2") (pinfunction "2_2") (pintype "passive"))
      (node (ref "C102") (pin "2") (pinfunction "2_2") (pintype "passive"))
      (node (ref "C103") (pin "2") (pinfunction "2_2") (pintype "passive"))
      (node (ref "C104") (pin "2") (pinfunction "2_2") (pintype "passive"))
      (node (ref "C105") (pin "2") (pinfunction "2_2") (pintype "passive"))
      (node (ref "C2") (pin "2") (pinfunction "2_2") (pintype "passive"))
      (node (ref "C3") (pin "2") (pinfunction "2_2") (pintype "passive"))
      (node (ref "C4") (pin "2") (pinfunction "2_2") (pintype "passive"))
      (node (ref "C5") (pin "2") (pinfunction "2_2") (pintype "passive"))
      (node (ref "C6") (pin "2") (pinfunction "2_2") (pintype "passive"))
      (node (ref "C7") (pin "2") (pinfunction "2_2") (pintype "passive"))
      (node (ref "C8") (pin "2") (pinfunction "2_2") (pintype "passive"))
      (node (ref "C9") (pin "2") (pinfunction "2_2") (pintype "passive"))
      (node (ref "GND") (pin "MP") (pinfunction "MP_MP") (pintype "passive"))
      (node (ref "GND1") (pin "MP") (pinfunction "MP_MP") (pintype "passive"))
      (node (ref "IC1") (pin "11") (pinfunction "GND_11") (pintype "bidirectional"))
      (node (ref "IC1") (pin "12") (pinfunction "GND2_12") (pintype "bidirectional"))
      (node (ref "IC1") (pin "13") (pinfunction "GND3_13") (pintype "bidirectional"))
      (node (ref "IC100") (pin "11") (pinfunction "GND_11") (pintype "bidirectional"))
      (node (ref "IC100") (pin "12") (pinfunction "GND2_12") (pintype "bidirectional"))
      (node (ref "IC100") (pin "13") (pinfunction "GND3_13") (pintype "bidirectional"))
      (node (ref "IC2") (pin "100") (pinfunction "VSSIO_5_100") (pintype "passive"))
      (node (ref "IC2") (pin "21") (pinfunction "VSSINT_1_21") (pintype "passive"))
      (node (ref "IC2") (pin "31") (pinfunction "VSSINT_2_31") (pintype "passive"))
      (node (ref "IC2") (pin "44") (pinfunction "VSSINT_3_44") (pintype "passive"))
      (node (ref "IC2") (pin "62") (pinfunction "VSSIO_1_62") (pintype "passive"))
      (node (ref "IC2") (pin "69") (pinfunction "VSSIO_2_69") (pintype "passive"))
      (node (ref "IC2") (pin "75") (pinfunction "VSSIO_3_75") (pintype "passive"))
      (node (ref "IC2") (pin "84") (pinfunction "VSSIO_4_84") (pintype "passive"))
      (node (ref "IC3") (pin "11") (pinfunction "GND_11") (pintype "bidirectional"))
      (node (ref "IC3") (pin "12") (pinfunction "GND2_12") (pintype "bidirectional"))
      (node (ref "IC3") (pin "13") (pinfunction "GND3_13") (pintype "bidirectional"))
      (node (ref "IC4") (pin "11") (pinfunction "GND_11") (pintype "bidirectional"))
      (node (ref "IC4") (pin "12") (pinfunction "GND2_12") (pintype "bidirectional"))
      (node (ref "IC4") (pin "13") (pinfunction "GND3_13") (pintype "bidirectional"))
      (node (ref "IC5") (pin "11") (pinfunction "GND_11") (pintype "bidirectional"))
      (node (ref "IC5") (pin "12") (pinfunction "GND2_12") (pintype "bidirectional"))
      (node (ref "IC5") (pin "13") (pinfunction "GND3_13") (pintype "bidirectional"))
      (node (ref "IC6") (pin "1") (pinfunction "GND_1") (pintype "passive"))
      (node (ref "JTAG-GND") (pin "MP") (pinfunction "MP_MP") (pintype "passive"))
      (node (ref "LED1") (pin "K") (pinfunction "C_K") (pintype "passive"))
      (node (ref "PLA-SOCKET") (pin "16") (pinfunction "GND_16") (pintype "bidirectional"))
      (node (ref "PLA-SOCKET") (pin "33") (pinfunction "GND2_33") (pintype "bidirectional"))
      (node (ref "PLA-SOCKET") (pin "48") (pinfunction "GND3_48") (pintype "bidirectional"))
    )
    (net (code "113") (name "Net-(IC2-PB00_08)") (class "Default")
      (node (ref "CLK") (pin "MP") (pinfunction "MP_MP") (pintype "passive"))
      (node (ref "IC2") (pin "22") (pinfunction "PB00_08_22") (pintype "bidirectional"))
    )
    (net (code "114") (name "Net-(IC2-PB00_13)") (class "Default")
      (node (ref "IC2") (pin "27") (pinfunction "PB00_13_27") (pintype "bidirectional"))
      (node (ref "MISC3") (pin "MP") (pinfunction "MP_MP") (pintype "passive"))
    )
    (net (code "115") (name "Net-(IC2-PB01_05)") (class "Default")
      (node (ref "IC2") (pin "96") (pinfunction "PB01_05_96") (pintype "bidirectional"))
      (node (ref "MISC2") (pin "MP") (pinfunction "MP_MP") (pintype "passive"))
      (node (ref "R1") (pin "1") (pinfunction "1_1") (pintype "passive"))
    )
    (net (code "116") (name "Net-(IC2-PB02_16)") (class "Default")
      (node (ref "IC2") (pin "58") (pinfunction "PB02_16_58") (pintype "bidirectional"))
      (node (ref "MISC1") (pin "MP") (pinfunction "MP_MP") (pintype "passive"))
    )
    (net (code "117") (name "Net-(IC2-TCK)") (class "Default")
      (node (ref "IC2") (pin "48") (pinfunction "TCK_48") (pintype "input"))
      (node (ref "TCK") (pin "MP") (pinfunction "MP_MP") (pintype "passive"))
    )
    (net (code "118") (name "Net-(IC2-TDI)") (class "Default")
      (node (ref "IC2") (pin "45") (pinfunction "TDI_45") (pintype "input"))
      (node (ref "TDI") (pin "MP") (pinfunction "MP_MP") (pintype "passive"))
    )
    (net (code "119") (name "Net-(IC2-TDO)") (class "Default")
      (node (ref "IC2") (pin "83") (pinfunction "TDO_83") (pintype "output"))
      (node (ref "TDO") (pin "MP") (pinfunction "MP_MP") (pintype "passive"))
    )
    (net (code "120") (name "Net-(IC2-TMS)") (class "Default")
      (node (ref "IC2") (pin "47") (pinfunction "TMS_47") (pintype "input"))
      (node (ref "TMS") (pin "MP") (pinfunction "MP_MP") (pintype "passive"))
    )
    (net (code "121") (name "Net-(LED1-PadA)") (class "Default")
      (node (ref "LED1") (pin "A") (pinfunction "A_A") (pintype "passive"))
      (node (ref "R1") (pin "2") (pinfunction "2_2") (pintype "passive"))
    )
    (net (code "122") (name "Net-(PLA-SOCKET-A0)") (class "Default")
      (node (ref "PLA-SOCKET") (pin "51") (pinfunction "A0_51") (pintype "bidirectional"))
      (node (ref "R117") (pin "1") (pinfunction "1_1") (pintype "passive"))
    )
    (net (code "123") (name "Net-(PLA-SOCKET-A1)") (class "Default")
      (node (ref "PLA-SOCKET") (pin "52") (pinfunction "A1_52") (pintype "bidirectional"))
      (node (ref "R116") (pin "1") (pinfunction "1_1") (pintype "passive"))
    )
    (net (code "124") (name "Net-(PLA-SOCKET-A2)") (class "Default")
      (node (ref "PLA-SOCKET") (pin "53") (pinfunction "A2_53") (pintype "bidirectional"))
      (node (ref "R115") (pin "1") (pinfunction "1_1") (pintype "passive"))
    )
    (net (code "125") (name "Net-(PLA-SOCKET-A3)") (class "Default")
      (node (ref "PLA-SOCKET") (pin "54") (pinfunction "A3_54") (pintype "bidirectional"))
      (node (ref "R114") (pin "1") (pinfunction "1_1") (pintype "passive"))
    )
    (net (code "126") (name "Net-(PLA-SOCKET-A4)") (class "Default")
      (node (ref "PLA-SOCKET") (pin "55") (pinfunction "A4_55") (pintype "bidirectional"))
      (node (ref "R113") (pin "1") (pinfunction "1_1") (pintype "passive"))
    )
    (net (code "127") (name "Net-(PLA-SOCKET-A5)") (class "Default")
      (node (ref "PLA-SOCKET") (pin "56") (pinfunction "A5_56") (pintype "bidirectional"))
      (node (ref "R112") (pin "1") (pinfunction "1_1") (pintype "passive"))
    )
    (net (code "128") (name "Net-(PLA-SOCKET-A6)") (class "Default")
      (node (ref "PLA-SOCKET") (pin "57") (pinfunction "A6_57") (pintype "bidirectional"))
      (node (ref "R111") (pin "1") (pinfunction "1_1") (pintype "passive"))
    )
    (net (code "129") (name "Net-(PLA-SOCKET-A7)") (class "Default")
      (node (ref "PLA-SOCKET") (pin "58") (pinfunction "A7_58") (pintype "bidirectional"))
      (node (ref "R110") (pin "1") (pinfunction "1_1") (pintype "passive"))
    )
    (net (code "130") (name "Net-(PLA-SOCKET-A8)") (class "Default")
      (node (ref "PLA-SOCKET") (pin "59") (pinfunction "A8_59") (pintype "bidirectional"))
      (node (ref "R109") (pin "1") (pinfunction "1_1") (pintype "passive"))
    )
    (net (code "131") (name "Net-(PLA-SOCKET-A9)") (class "Default")
      (node (ref "PLA-SOCKET") (pin "60") (pinfunction "A9_60") (pintype "bidirectional"))
      (node (ref "R108") (pin "1") (pinfunction "1_1") (pintype "passive"))
    )
    (net (code "132") (name "Net-(PLA-SOCKET-A10)") (class "Default")
      (node (ref "PLA-SOCKET") (pin "61") (pinfunction "A10_61") (pintype "bidirectional"))
      (node (ref "R106") (pin "1") (pinfunction "1_1") (pintype "passive"))
    )
    (net (code "133") (name "Net-(PLA-SOCKET-A11)") (class "Default")
      (node (ref "PLA-SOCKET") (pin "62") (pinfunction "A11_62") (pintype "bidirectional"))
      (node (ref "R104") (pin "1") (pinfunction "1_1") (pintype "passive"))
    )
    (net (code "134") (name "Net-(PLA-SOCKET-A12)") (class "Default")
      (node (ref "PLA-SOCKET") (pin "63") (pinfunction "A12_63") (pintype "bidirectional"))
      (node (ref "R102") (pin "1") (pinfunction "1_1") (pintype "passive"))
    )
    (net (code "135") (name "Net-(PLA-SOCKET-A13)") (class "Default")
      (node (ref "PLA-SOCKET") (pin "1") (pinfunction "A13_1") (pintype "bidirectional"))
      (node (ref "R100") (pin "2") (pinfunction "2_2") (pintype "passive"))
    )
    (net (code "136") (name "Net-(PLA-SOCKET-A14)") (class "Default")
      (node (ref "PLA-SOCKET") (pin "2") (pinfunction "A14_2") (pintype "bidirectional"))
      (node (ref "R101") (pin "2") (pinfunction "2_2") (pintype "passive"))
    )
    (net (code "137") (name "Net-(PLA-SOCKET-A15)") (class "Default")
      (node (ref "PLA-SOCKET") (pin "3") (pinfunction "A15_3") (pintype "bidirectional"))
      (node (ref "R103") (pin "2") (pinfunction "2_2") (pintype "passive"))
    )
    (net (code "138") (name "Net-(PLA-SOCKET-AEC)") (class "Default")
      (node (ref "PLA-SOCKET") (pin "38") (pinfunction "AEC_38") (pintype "bidirectional"))
      (node (ref "R121") (pin "1") (pinfunction "1_1") (pintype "passive"))
    )
    (net (code "139") (name "Net-(PLA-SOCKET-BA)") (class "Default")
      (node (ref "PLA-SOCKET") (pin "39") (pinfunction "BA_39") (pintype "bidirectional"))
      (node (ref "R120") (pin "1") (pinfunction "1_1") (pintype "passive"))
    )
    (net (code "140") (name "Net-(PLA-SOCKET-MA0)") (class "Default")
      (node (ref "PLA-SOCKET") (pin "26") (pinfunction "MA0_26") (pintype "bidirectional"))
      (node (ref "R9") (pin "2") (pinfunction "2_2") (pintype "passive"))
    )
    (net (code "141") (name "Net-(PLA-SOCKET-MA1)") (class "Default")
      (node (ref "PLA-SOCKET") (pin "29") (pinfunction "MA1_29") (pintype "bidirectional"))
      (node (ref "R6") (pin "2") (pinfunction "2_2") (pintype "passive"))
    )
    (net (code "142") (name "Net-(PLA-SOCKET-MA2)") (class "Default")
      (node (ref "PLA-SOCKET") (pin "27") (pinfunction "MA2_27") (pintype "bidirectional"))
      (node (ref "R8") (pin "2") (pinfunction "2_2") (pintype "passive"))
    )
    (net (code "143") (name "Net-(PLA-SOCKET-MA3)") (class "Default")
      (node (ref "PLA-SOCKET") (pin "25") (pinfunction "MA3_25") (pintype "bidirectional"))
      (node (ref "R11") (pin "2") (pinfunction "2_2") (pintype "passive"))
    )
    (net (code "144") (name "Net-(PLA-SOCKET-MA4)") (class "Default")
      (node (ref "PLA-SOCKET") (pin "28") (pinfunction "MA4_28") (pintype "bidirectional"))
      (node (ref "R7") (pin "2") (pinfunction "2_2") (pintype "passive"))
    )
    (net (code "145") (name "Net-(PLA-SOCKET-MA5)") (class "Default")
      (node (ref "PLA-SOCKET") (pin "30") (pinfunction "MA5_30") (pintype "bidirectional"))
      (node (ref "R5") (pin "2") (pinfunction "2_2") (pintype "passive"))
    )
    (net (code "146") (name "Net-(PLA-SOCKET-MA6)") (class "Default")
      (node (ref "PLA-SOCKET") (pin "24") (pinfunction "MA6_24") (pintype "bidirectional"))
      (node (ref "R12") (pin "2") (pinfunction "2_2") (pintype "passive"))
    )
    (net (code "147") (name "Net-(PLA-SOCKET-MA7)") (class "Default")
      (node (ref "PLA-SOCKET") (pin "31") (pinfunction "MA7_31") (pintype "bidirectional"))
      (node (ref "R4") (pin "2") (pinfunction "2_2") (pintype "passive"))
    )
    (net (code "148") (name "Net-(PLA-SOCKET-NMI)") (class "Default")
      (node (ref "PLA-SOCKET") (pin "8") (pinfunction "NMI_8") (pintype "bidirectional"))
      (node (ref "R30") (pin "2") (pinfunction "2_2") (pintype "passive"))
    )
    (net (code "149") (name "Net-(PLA-SOCKET-PHI0)") (class "Default")
      (node (ref "PLA-SOCKET") (pin "37") (pinfunction "PHI0_37") (pintype "bidirectional"))
      (node (ref "R122") (pin "1") (pinfunction "1_1") (pintype "passive"))
    )
    (net (code "150") (name "Net-(PLA-SOCKET-RAMR{slash}_W)") (class "Default")
      (node (ref "PLA-SOCKET") (pin "23") (pinfunction "RAMR/_W_23") (pintype "bidirectional"))
      (node (ref "R13") (pin "2") (pinfunction "2_2") (pintype "passive"))
    )
    (net (code "151") (name "Net-(PLA-SOCKET-RESTORE)") (class "Default")
      (node (ref "PLA-SOCKET") (pin "9") (pinfunction "RESTORE_9") (pintype "bidirectional"))
      (node (ref "R29") (pin "2") (pinfunction "2_2") (pintype "passive"))
    )
    (net (code "152") (name "Net-(PLA-SOCKET-R{slash}_W)") (class "Default")
      (node (ref "PLA-SOCKET") (pin "4") (pinfunction "R/_W_4") (pintype "bidirectional"))
      (node (ref "R105") (pin "2") (pinfunction "2_2") (pintype "passive"))
    )
    (net (code "153") (name "Net-(PLA-SOCKET-VA6)") (class "Default")
      (node (ref "PLA-SOCKET") (pin "41") (pinfunction "VA6_41") (pintype "bidirectional"))
      (node (ref "R119") (pin "1") (pinfunction "1_1") (pintype "passive"))
    )
    (net (code "154") (name "Net-(PLA-SOCKET-VA7)") (class "Default")
      (node (ref "PLA-SOCKET") (pin "42") (pinfunction "VA7_42") (pintype "bidirectional"))
      (node (ref "R118") (pin "1") (pinfunction "1_1") (pintype "passive"))
    )
    (net (code "155") (name "Net-(PLA-SOCKET-_BASIC)") (class "Default")
      (node (ref "PLA-SOCKET") (pin "14") (pinfunction "_BASIC_14") (pintype "bidirectional"))
      (node (ref "R24") (pin "2") (pinfunction "2_2") (pintype "passive"))
    )
    (net (code "156") (name "Net-(PLA-SOCKET-_CAS)") (class "Default")
      (node (ref "PLA-SOCKET") (pin "35") (pinfunction "_CAS_35") (pintype "bidirectional"))
      (node (ref "R124") (pin "1") (pinfunction "1_1") (pintype "passive"))
    )
    (net (code "157") (name "Net-(PLA-SOCKET-_CASRAM)") (class "Default")
      (node (ref "PLA-SOCKET") (pin "22") (pinfunction "_CASRAM_22") (pintype "bidirectional"))
      (node (ref "R15") (pin "2") (pinfunction "2_2") (pintype "passive"))
    )
    (net (code "158") (name "Net-(PLA-SOCKET-_CHAREN)") (class "Default")
      (node (ref "PLA-SOCKET") (pin "7") (pinfunction "_CHAREN_7") (pintype "bidirectional"))
      (node (ref "R31") (pin "2") (pinfunction "2_2") (pintype "passive"))
    )
    (net (code "159") (name "Net-(PLA-SOCKET-_CHAROM)") (class "Default")
      (node (ref "PLA-SOCKET") (pin "13") (pinfunction "_CHAROM_13") (pintype "bidirectional"))
      (node (ref "R25") (pin "2") (pinfunction "2_2") (pintype "passive"))
    )
    (net (code "160") (name "Net-(PLA-SOCKET-_CIA1)") (class "Default")
      (node (ref "PLA-SOCKET") (pin "34") (pinfunction "_CIA1_34") (pintype "bidirectional"))
      (node (ref "R125") (pin "1") (pinfunction "1_1") (pintype "passive"))
    )
    (net (code "161") (name "Net-(PLA-SOCKET-_CIA2)") (class "Default")
      (node (ref "PLA-SOCKET") (pin "12") (pinfunction "_CIA2_12") (pintype "bidirectional"))
      (node (ref "R26") (pin "2") (pinfunction "2_2") (pintype "passive"))
    )
    (net (code "162") (name "Net-(PLA-SOCKET-_COLRAM)") (class "Default")
      (node (ref "PLA-SOCKET") (pin "17") (pinfunction "_COLRAM_17") (pintype "bidirectional"))
      (node (ref "R20") (pin "2") (pinfunction "2_2") (pintype "passive"))
    )
    (net (code "163") (name "Net-(PLA-SOCKET-_EXROM)") (class "Default")
      (node (ref "PLA-SOCKET") (pin "46") (pinfunction "_EXROM_46") (pintype "bidirectional"))
      (node (ref "R18") (pin "1") (pinfunction "1_1") (pintype "passive"))
    )
    (net (code "164") (name "Net-(PLA-SOCKET-_GAME)") (class "Default")
      (node (ref "PLA-SOCKET") (pin "47") (pinfunction "_GAME_47") (pintype "bidirectional"))
      (node (ref "R19") (pin "1") (pinfunction "1_1") (pintype "passive"))
    )
    (net (code "165") (name "Net-(PLA-SOCKET-_HIRAM)") (class "Default")
      (node (ref "PLA-SOCKET") (pin "6") (pinfunction "_HIRAM_6") (pintype "bidirectional"))
      (node (ref "R32") (pin "2") (pinfunction "2_2") (pintype "passive"))
    )
    (net (code "166") (name "Net-(PLA-SOCKET-_I{slash}O1)") (class "Default")
      (node (ref "PLA-SOCKET") (pin "49") (pinfunction "_I/O1_49") (pintype "bidirectional"))
      (node (ref "R21") (pin "1") (pinfunction "1_1") (pintype "passive"))
    )
    (net (code "167") (name "Net-(PLA-SOCKET-_I{slash}O2)") (class "Default")
      (node (ref "PLA-SOCKET") (pin "45") (pinfunction "_I/O2_45") (pintype "bidirectional"))
      (node (ref "R17") (pin "1") (pinfunction "1_1") (pintype "passive"))
    )
    (net (code "168") (name "Net-(PLA-SOCKET-_KERNAL)") (class "Default")
      (node (ref "PLA-SOCKET") (pin "15") (pinfunction "_KERNAL_15") (pintype "bidirectional"))
      (node (ref "R23") (pin "2") (pinfunction "2_2") (pintype "passive"))
    )
    (net (code "169") (name "Net-(PLA-SOCKET-_LORAM)") (class "Default")
      (node (ref "PLA-SOCKET") (pin "5") (pinfunction "_LORAM_5") (pintype "bidirectional"))
      (node (ref "R107") (pin "2") (pinfunction "2_2") (pintype "passive"))
    )
    (net (code "170") (name "Net-(PLA-SOCKET-_RAS)") (class "Default")
      (node (ref "PLA-SOCKET") (pin "36") (pinfunction "_RAS_36") (pintype "bidirectional"))
      (node (ref "R123") (pin "1") (pinfunction "1_1") (pintype "passive"))
    )
    (net (code "171") (name "Net-(PLA-SOCKET-_ROMH)") (class "Default")
      (node (ref "PLA-SOCKET") (pin "50") (pinfunction "_ROMH_50") (pintype "bidirectional"))
      (node (ref "R22") (pin "1") (pinfunction "1_1") (pintype "passive"))
    )
    (net (code "172") (name "Net-(PLA-SOCKET-_ROML)") (class "Default")
      (node (ref "PLA-SOCKET") (pin "44") (pinfunction "_ROML_44") (pintype "bidirectional"))
      (node (ref "R16") (pin "1") (pinfunction "1_1") (pintype "passive"))
    )
    (net (code "173") (name "Net-(PLA-SOCKET-_SID)") (class "Default")
      (node (ref "PLA-SOCKET") (pin "43") (pinfunction "_SID_43") (pintype "bidirectional"))
      (node (ref "R14") (pin "1") (pinfunction "1_1") (pintype "passive"))
    )
    (net (code "174") (name "Net-(PLA-SOCKET-_VA14)") (class "Default")
      (node (ref "PLA-SOCKET") (pin "10") (pinfunction "_VA14_10") (pintype "bidirectional"))
      (node (ref "R28") (pin "2") (pinfunction "2_2") (pintype "passive"))
    )
    (net (code "175") (name "Net-(PLA-SOCKET-_VA15)") (class "Default")
      (node (ref "PLA-SOCKET") (pin "11") (pinfunction "_VA15_11") (pintype "bidirectional"))
      (node (ref "R27") (pin "2") (pinfunction "2_2") (pintype "passive"))
    )
    (net (code "176") (name "Net-(PLA-SOCKET-_VIC)") (class "Default")
      (node (ref "PLA-SOCKET") (pin "40") (pinfunction "_VIC_40") (pintype "bidirectional"))
      (node (ref "R10") (pin "1") (pinfunction "1_1") (pintype "passive"))
    )
    (net (code "177") (name "unconnected-(PLA-SOCKET-P$18-Pad18)") (class "Default")
      (node (ref "PLA-SOCKET") (pin "18") (pinfunction "P$18_18") (pintype "bidirectional"))
    )
    (net (code "178") (name "unconnected-(PLA-SOCKET-P$19-Pad19)") (class "Default")
      (node (ref "PLA-SOCKET") (pin "19") (pinfunction "P$19_19") (pintype "bidirectional"))
    )
    (net (code "179") (name "unconnected-(PLA-SOCKET-P$20-Pad20)") (class "Default")
      (node (ref "PLA-SOCKET") (pin "20") (pinfunction "P$20_20") (pintype "bidirectional"))
    )
    (net (code "180") (name "unconnected-(PLA-SOCKET-P$21-Pad21)") (class "Default")
      (node (ref "PLA-SOCKET") (pin "21") (pinfunction "P$21_21") (pintype "bidirectional"))
    )
    (net (code "181") (name "unconnected-(PLA-SOCKET-P$32-Pad32)") (class "Default")
      (node (ref "PLA-SOCKET") (pin "32") (pinfunction "P$32_32") (pintype "bidirectional"))
    )
  )
)
